# M1-MCU.net
KiCad netlist of a schematic drawn in Altium Designer
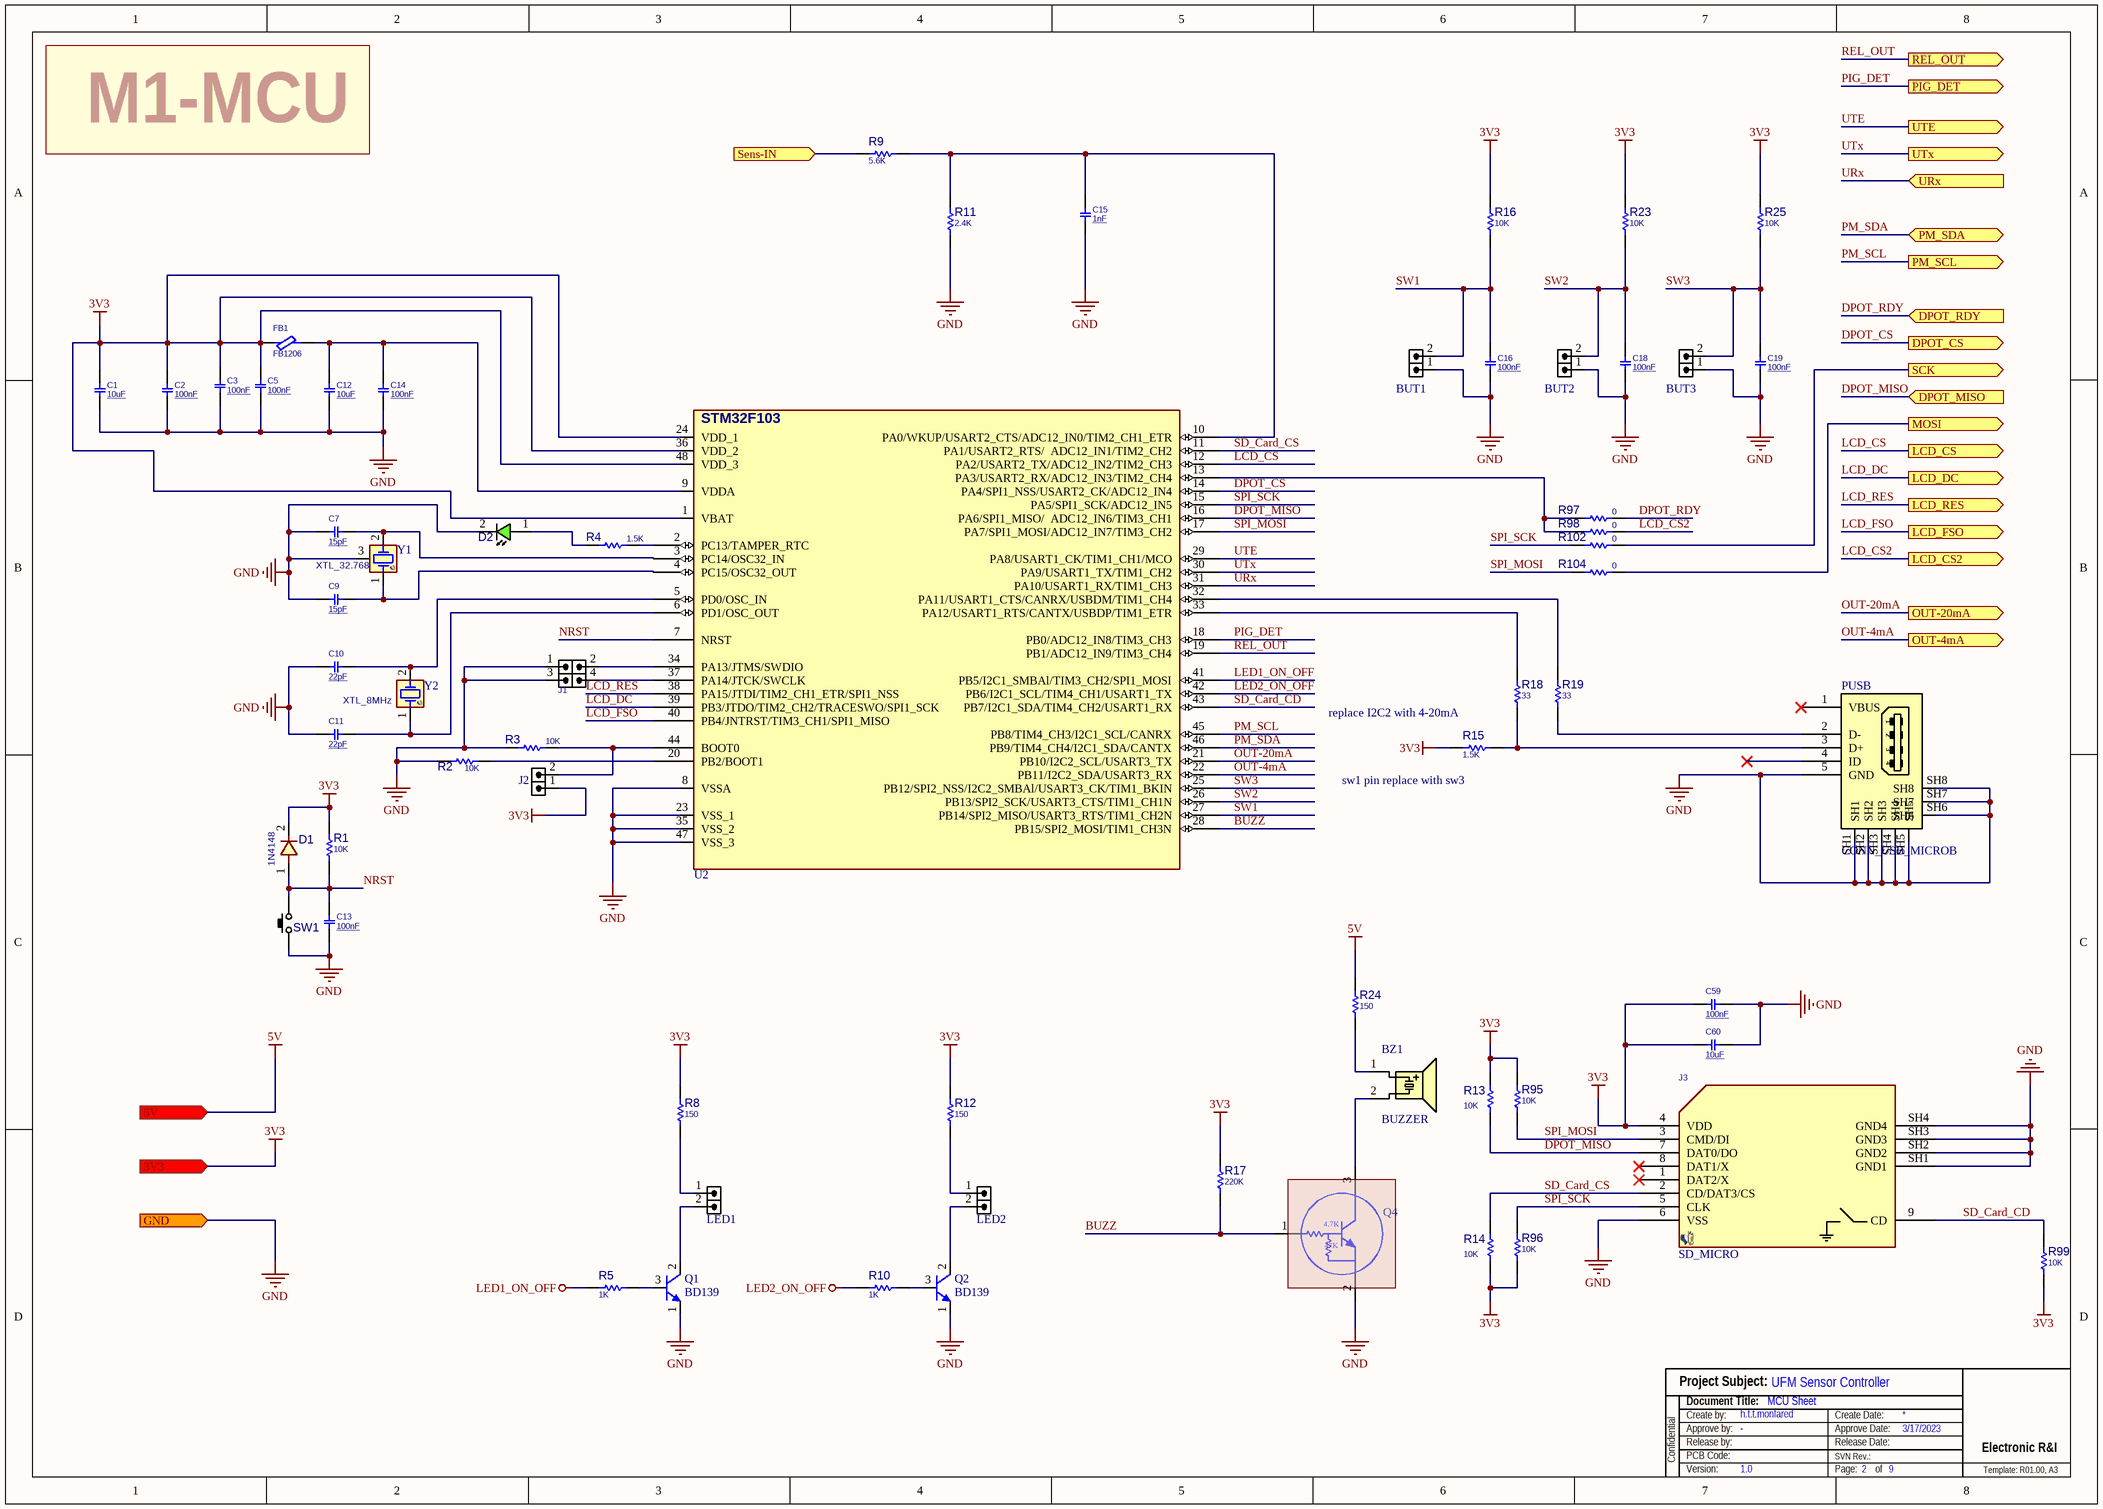
[diagram p0: M1-MCU.SchDoc]

(export (version "E")
  (design (tool "Eeschema 10.0.6"))
  (components
    (comp (ref "BUT1")
      (value "HDRM2")
      (footprint "TMS2")
      (description "CONN, HEADER, Male, pitch: 2.54mm, 2POS")
      (libsource (lib "conn_header_2.54_st") (part "HDR_M_1X2"))
    )
    (comp (ref "BUT2")
      (value "HDRM2")
      (footprint "TMS2")
      (description "CONN, HEADER, Male, pitch: 2.54mm, 2POS")
      (libsource (lib "conn_header_2.54_st") (part "HDR_M_1X2"))
    )
    (comp (ref "BUT3")
      (value "HDRM2")
      (footprint "TMS2")
      (description "CONN, HEADER, Male, pitch: 2.54mm, 2POS")
      (libsource (lib "conn_header_2.54_st") (part "HDR_M_1X2"))
    )
    (comp (ref "BZ1")
      (value "BUZZER")
      (footprint "BZ_C12")
      (description "Buzzer, 12X8.5mm, Magnetic Transducer")
      (fields
        (field (name "MANF") "Buerklin, CUI")
        (field (name "MANF_P#") "CM12P, MT03-H1BHP, BMT1205XH7.5, CEM-1201(50)")
      )
      (libsource (lib "audio_mic_spk") (part "BUZZER_C12"))
    )
    (comp (ref "C1")
      (value "10uF")
      (footprint "C1206")
      (description "CAP, MLCC, 1nF, 50V, C0G, 10%, 0402")
      (fields (field (name "MANF_P#") "MANF_PART#") (field (name "MANF") "Murata"))
      (libsource (lib "passive_smd") (part "CAP_SMD_MLCC"))
    )
    (comp (ref "C2")
      (value "100nF")
      (footprint "C1206")
      (description "CAP, MLCC, 1nF, 50V, C0G, 10%, 0402")
      (fields (field (name "MANF_P#") "MANF_PART#") (field (name "MANF") "Murata"))
      (libsource (lib "passive") (part "CAP_SMD_MLCC"))
    )
    (comp (ref "C3")
      (value "100nF")
      (footprint "C1206")
      (description "CAP, MLCC, 1nF, 50V, C0G, 10%, 0402")
      (fields (field (name "MANF_P#") "MANF_PART#") (field (name "MANF") "Murata"))
      (libsource (lib "passive") (part "CAP_SMD_MLCC"))
    )
    (comp (ref "C5")
      (value "100nF")
      (footprint "C1206")
      (description "CAP, MLCC, 1nF, 50V, C0G, 10%, 0402")
      (fields (field (name "MANF_P#") "MANF_PART#") (field (name "MANF") "Murata"))
      (libsource (lib "passive") (part "CAP_SMD_MLCC"))
    )
    (comp (ref "C7")
      (value "15pF")
      (footprint "C1206")
      (description "CAP, MLCC, 1nF, 50V, C0G, 10%, 0402")
      (fields (field (name "MANF_P#") "MANF_PART#") (field (name "MANF") "Murata"))
      (libsource (lib "passive") (part "CAP_SMD_MLCC"))
    )
    (comp (ref "C9")
      (value "15pF")
      (footprint "C1206")
      (description "CAP, MLCC, 1nF, 50V, C0G, 10%, 0402")
      (fields (field (name "MANF_P#") "MANF_PART#") (field (name "MANF") "Murata"))
      (libsource (lib "passive") (part "CAP_SMD_MLCC"))
    )
    (comp (ref "C10")
      (value "22pF")
      (footprint "C1206")
      (description "CAP, MLCC, 1nF, 50V, C0G, 10%, 0402")
      (fields (field (name "MANF_P#") "MANF_PART#") (field (name "MANF") "Murata"))
      (libsource (lib "passive") (part "CAP_SMD_MLCC"))
    )
    (comp (ref "C11")
      (value "22pF")
      (footprint "C1206")
      (description "CAP, MLCC, 1nF, 50V, C0G, 10%, 0402")
      (fields (field (name "MANF_P#") "MANF_PART#") (field (name "MANF") "Murata"))
      (libsource (lib "passive") (part "CAP_SMD_MLCC"))
    )
    (comp (ref "C12")
      (value "10uF")
      (footprint "C1206")
      (description "CAP, MLCC, 1nF, 50V, C0G, 10%, 0402")
      (fields (field (name "MANF_P#") "MANF_PART#") (field (name "MANF") "Murata"))
      (libsource (lib "passive_smd") (part "CAP_SMD_MLCC"))
    )
    (comp (ref "C13")
      (value "100nF")
      (footprint "C1206")
      (description "CAP, MLCC, 1nF, 50V, C0G, 10%, 0402")
      (fields (field (name "MANF_P#") "MANF_PART#") (field (name "MANF") "Murata"))
      (libsource (lib "passive") (part "CAP_SMD_MLCC"))
    )
    (comp (ref "C14")
      (value "100nF")
      (footprint "C1206")
      (description "CAP, MLCC, 1nF, 50V, C0G, 10%, 0402")
      (fields (field (name "MANF_P#") "MANF_PART#") (field (name "MANF") "Murata"))
      (libsource (lib "passive") (part "CAP_SMD_MLCC"))
    )
    (comp (ref "C15")
      (value "1nF")
      (footprint "C1206")
      (description "CAP, MLCC, 1nF, 50V, C0G, 10%, 0402")
      (fields (field (name "MANF_P#") "MANF_PART#") (field (name "MANF") "Murata"))
      (libsource (lib "passive_smd") (part "CAP_SMD_MLCC"))
    )
    (comp (ref "C16")
      (value "100nF")
      (footprint "C1206")
      (description "CAP, MLCC, 1nF, 50V, C0G, 10%, 0402")
      (fields (field (name "MANF_P#") "MANF_PART#") (field (name "MANF") "Murata"))
      (libsource (lib "passive_smd") (part "CAP_SMD_MLCC"))
    )
    (comp (ref "C18")
      (value "100nF")
      (footprint "C1206")
      (description "CAP, MLCC, 1nF, 50V, C0G, 10%, 0402")
      (fields (field (name "MANF_P#") "MANF_PART#") (field (name "MANF") "Murata"))
      (libsource (lib "passive_smd") (part "CAP_SMD_MLCC"))
    )
    (comp (ref "C19")
      (value "100nF")
      (footprint "C1206")
      (description "CAP, MLCC, 1nF, 50V, C0G, 10%, 0402")
      (fields (field (name "MANF_P#") "MANF_PART#") (field (name "MANF") "Murata"))
      (libsource (lib "passive_smd") (part "CAP_SMD_MLCC"))
    )
    (comp (ref "C59")
      (value "100nF")
      (footprint "C1206")
      (description "CAP, MLCC, 1nF, 50V, C0G, 10%, 0402")
      (fields (field (name "MANF_P#") "MANF_PART#") (field (name "MANF") "Murata"))
      (libsource (lib "passive_smd") (part "CAP_SMD_MLCC"))
    )
    (comp (ref "C60")
      (value "10uF")
      (footprint "C1206")
      (description "CAP, MLCC, 1nF, 50V, C0G, 10%, 0402")
      (fields (field (name "MANF_P#") "MANF_PART#") (field (name "MANF") "Murata"))
      (libsource (lib "passive_smd") (part "CAP_SMD_MLCC"))
    )
    (comp (ref "D1")
      (value "1N4148")
      (footprint "D_AX02_DO35")
      (description "DIODE, FAST SWTICHING, THD")
      (fields (field (name "MANF") "MANF"))
      (libsource (lib "diode") (part "DIODE_THD_1N4148_DO35"))
    )
    (comp (ref "D2")
      (value "LED1206GRN")
      (footprint "LED1206GRN")
      (description "LED, SMD, 1206, GREEN")
      (libsource (lib "led(diode)") (part "LED_SMD_1206_GRN"))
    )
    (comp (ref "FB1")
      (value "FB1206")
      (footprint "L1206")
      (description "FERRITE_Bead, 1206, 6A, 9mOhm, 33@100MHz")
      (fields (field (name "MANF") "Murata") (field (name "MANF_P#") "BLM31PG330SN1L"))
      (libsource (lib "emi_filter") (part "FBEAD_SMD_BLM31PG330"))
    )
    (comp (ref "J1")
      (value "HDRM_2X2")
      (footprint "HDR_M_2X2")
      (description "CONN, HEADER, Male, pitch: 2.54mm, 4POS")
      (fields (field (name "MANF_P#") "MANF_PART#") (field (name "MANF") "MANF"))
      (libsource (lib "conn_header_2.54_st") (part "HDR_M_2X2"))
    )
    (comp (ref "J2")
      (value "HDRM2")
      (footprint "HDR_M_1X2")
      (description "CONN, HEADER, Male, pitch: 2.54mm, 2POS")
      (libsource (lib "conn_header_2.54_st") (part "HDR_M_1X2"))
    )
    (comp (ref "J3")
      (value "SD_MICRO")
      (footprint "SDMICRO_AT")
      (description "SD MICRO exist in Iran, Attend 112J-TDAR-R01")
      (fields (field (name "MANF") "Attend") (field (name "MANF_P#") "112J-TDAR-R01"))
      (libsource (lib "socket_card") (part "SOCKET_SDMICRO_AT"))
    )
    (comp (ref "LED1")
      (value "HDRM2")
      (footprint "TMS2")
      (description "CONN, HEADER, Male, pitch: 2.54mm, 2POS")
      (libsource (lib "") (part "HDR_M_1X2_1"))
    )
    (comp (ref "LED2")
      (value "HDRM2")
      (footprint "TMS2")
      (description "CONN, HEADER, Male, pitch: 2.54mm, 2POS")
      (libsource (lib "") (part "HDR_M_1X2_1"))
    )
    (comp (ref "PUSB")
      (value "CONN_USB_MICROB")
      (footprint "USB_MICRO_B_BM_SHS")
      (description "CONN, USB, MICRO B, R/A, SMD, BOTTOM MOUNT")
      (fields (field (name "MANF_P#") "47346-0001") (field (name "MANF") "Molex"))
      (libsource (lib "conn_usb") (part "CONN_USB_MICRO_B_BM_SHS"))
    )
    (comp (ref "Q1")
      (value "BD139")
      (footprint "TO126_3")
      (description "BJT, NPN, 80V, 1.5A")
      (fields (field (name "MANF") "FAIRCHILD"))
      (libsource (lib "transistor_bjt") (part "NPN_BD139_TO126"))
    )
    (comp (ref "Q2")
      (value "BD139")
      (footprint "TO126_3")
      (description "BJT, NPN, 80V, 1.5A")
      (fields (field (name "MANF") "FAIRCHILD"))
      (libsource (lib "transistor_bjt") (part "NPN_BD139_TO126"))
    )
    (comp (ref "Q4")
      (value "BCR116")
      (footprint "SOT23:SOT23")
      (description "NPN Silicon Digital Transistor")
      (libsource (lib "BCR116") (part "BCR116"))
    )
    (comp (ref "R1")
      (value "10K")
      (footprint "R1206")
      (description "RESISTOR, SMD")
      (fields (field (name "MANF_P#") "RK73H1ETTP4701F") (field (name "MANF") "KOA SPEER"))
      (libsource (lib "passive") (part "RES_SMD"))
    )
    (comp (ref "R2")
      (value "10K")
      (footprint "R1206")
      (description "RESISTOR, SMD")
      (fields (field (name "MANF_P#") "RK73H1ETTP4701F") (field (name "MANF") "KOA SPEER"))
      (libsource (lib "passive") (part "RES_SMD"))
    )
    (comp (ref "R3")
      (value "10K")
      (footprint "R1206")
      (description "RESISTOR, SMD")
      (fields (field (name "MANF_P#") "RK73H1ETTP4701F") (field (name "MANF") "KOA SPEER"))
      (libsource (lib "passive") (part "RES_SMD"))
    )
    (comp (ref "R4")
      (value "1.5K")
      (footprint "R1206")
      (description "RESISTOR, SMD")
      (fields (field (name "MANF_P#") "RK73H1ETTP4701F") (field (name "MANF") "KOA SPEER"))
      (libsource (lib "passive") (part "RES_SMD"))
    )
    (comp (ref "R5")
      (value "1K")
      (footprint "R1206")
      (description "RESISTOR, SMD")
      (fields (field (name "MANF_P#") "RK73H1ETTP4701F") (field (name "MANF") "KOA SPEER"))
      (libsource (lib "passive") (part "RES_SMD"))
    )
    (comp (ref "R8")
      (value "150")
      (footprint "R1206")
      (description "RESISTOR, SMD")
      (fields (field (name "MANF_P#") "RK73H1ETTP4701F") (field (name "MANF") "KOA SPEER"))
      (libsource (lib "passive") (part "RES_SMD"))
    )
    (comp (ref "R9")
      (value "5.6K")
      (footprint "R1206")
      (description "RESISTOR, SMD")
      (libsource (lib "passive_smd") (part "RES_SMD"))
    )
    (comp (ref "R10")
      (value "1K")
      (footprint "R1206")
      (description "RESISTOR, SMD")
      (fields (field (name "MANF_P#") "RK73H1ETTP4701F") (field (name "MANF") "KOA SPEER"))
      (libsource (lib "passive") (part "RES_SMD"))
    )
    (comp (ref "R11")
      (value "2.4K")
      (footprint "R1206")
      (description "RESISTOR, SMD")
      (libsource (lib "passive_smd") (part "RES_SMD"))
    )
    (comp (ref "R12")
      (value "150")
      (footprint "R1206")
      (description "RESISTOR, SMD")
      (fields (field (name "MANF_P#") "RK73H1ETTP4701F") (field (name "MANF") "KOA SPEER"))
      (libsource (lib "passive") (part "RES_SMD"))
    )
    (comp (ref "R13")
      (value "10K")
      (footprint "R1206")
      (description "RESISTOR, SMD")
      (libsource (lib "passive_smd") (part "RES_SMD"))
    )
    (comp (ref "R14")
      (value "10K")
      (footprint "R1206")
      (description "RESISTOR, SMD")
      (libsource (lib "passive_smd") (part "RES_SMD"))
    )
    (comp (ref "R15")
      (value "1.5K")
      (footprint "R1206")
      (description "RESISTOR, SMD")
      (fields (field (name "MANF_P#") "RK73H1ETTP4701F") (field (name "MANF") "KOA SPEER"))
      (libsource (lib "passive") (part "RES_SMD"))
    )
    (comp (ref "R16")
      (value "10K")
      (footprint "R1206")
      (description "RESISTOR, SMD")
      (libsource (lib "passive_smd") (part "RES_SMD"))
    )
    (comp (ref "R17")
      (value "220K")
      (footprint "R1206")
      (description "RESISTOR, SMD")
      (libsource (lib "passive_smd") (part "RES_SMD"))
    )
    (comp (ref "R18")
      (value "33")
      (footprint "R1206")
      (description "RESISTOR, SMD")
      (fields (field (name "MANF_P#") "RK73H1ETTP4701F") (field (name "MANF") "KOA SPEER"))
      (libsource (lib "passive") (part "RES_SMD"))
    )
    (comp (ref "R19")
      (value "33")
      (footprint "R1206")
      (description "RESISTOR, SMD")
      (fields (field (name "MANF_P#") "RK73H1ETTP4701F") (field (name "MANF") "KOA SPEER"))
      (libsource (lib "passive") (part "RES_SMD"))
    )
    (comp (ref "R23")
      (value "10K")
      (footprint "R1206")
      (description "RESISTOR, SMD")
      (libsource (lib "passive_smd") (part "RES_SMD"))
    )
    (comp (ref "R24")
      (value "150")
      (footprint "R1206")
      (description "RESISTOR, SMD")
      (libsource (lib "passive_smd") (part "RES_SMD"))
    )
    (comp (ref "R25")
      (value "10K")
      (footprint "R1206")
      (description "RESISTOR, SMD")
      (libsource (lib "passive_smd") (part "RES_SMD"))
    )
    (comp (ref "R95")
      (value "10K")
      (footprint "R1206")
      (description "RESISTOR, SMD")
      (libsource (lib "passive_smd") (part "RES_SMD"))
    )
    (comp (ref "R96")
      (value "10K")
      (footprint "R1206")
      (description "RESISTOR, SMD")
      (libsource (lib "passive_smd") (part "RES_SMD"))
    )
    (comp (ref "R97")
      (value "0")
      (footprint "R1206")
      (description "RESISTOR, SMD")
      (libsource (lib "passive_smd") (part "RES_SMD"))
    )
    (comp (ref "R98")
      (value "0")
      (footprint "R1206")
      (description "RESISTOR, SMD")
      (libsource (lib "passive_smd") (part "RES_SMD"))
    )
    (comp (ref "R99")
      (value "10K")
      (footprint "R1206")
      (description "RESISTOR, SMD")
      (libsource (lib "passive_smd") (part "RES_SMD"))
    )
    (comp (ref "R102")
      (value "0")
      (footprint "R1206")
      (description "RESISTOR, SMD")
      (libsource (lib "passive_smd") (part "RES_SMD"))
    )
    (comp (ref "R104")
      (value "0")
      (footprint "R1206")
      (description "RESISTOR, SMD")
      (libsource (lib "passive_smd") (part "RES_SMD"))
    )
    (comp (ref "SW1")
      (value "PUSHBUTTON")
      (footprint "SWPBS_SPST_6X3X5")
      (description "SWITCH, PUSH BUTTON, TACTILE, SMD, SPST, 6X3.5X4.3mm")
      (fields (field (name "MANF") "Panasonic") (field (name "MANF_P#") "EVQ-PNF04M"))
      (libsource (lib "switch_tact_PUSHB") (part "SWPBS_SPST_6X3X4"))
    )
    (comp (ref "U2")
      (value "STM32F103")
      (footprint "QFG50_48")
      (description "MCU, STM32 ARM 32-bit, Cortex M3, 64KB FLASH, 20KB SRAM")
      (fields (field (name "MANF") "ST") (field (name "MANF_P#") "STM32F103C8T6"))
      (libsource (lib "mcu_stm32") (part "STM32F103C8T6_QFP48"))
    )
    (comp (ref "Y1")
      (value "XTL_32.768")
      (footprint "XTLT_RTC")
      (description "Crystal MOST POPULAR PACKAGE")
      (fields (field (name "MANF") "ABRACON") (field (name "MANF_P#") "AB26T-32.768KHZ"))
      (libsource (lib "crystal") (part "XTL_3_32.768_THD"))
    )
    (comp (ref "Y2")
      (value "XTL_8MHz")
      (footprint "XTL_2_11X5")
      (description "Crystal MOST POPULAR ABL HC49 PACKAGE")
      (fields (field (name "MANF") "ABRACON") (field (name "MANF_P#") "ABLS-8.000MHZ-B4-T"))
      (libsource (lib "crystal") (part "XTL_2_HC49_8MHz_SMD"))
    )
  )
  (nets
    (net (code "1") (name "/BUZZ") (class "Default")
      (node (ref "Q4") (pin "1") (pinfunction "B_1") (pintype "passive"))
      (node (ref "R17") (pin "1") (pinfunction "1_1") (pintype "passive"))
      (node (ref "U2") (pin "28") (pinfunction "PB15/SPI2_MOSI/TIM1_CH3N_28") (pintype "bidirectional"))
    )
    (net (code "2") (name "/DPOT_CS") (class "Default")
      (node (ref "U2") (pin "14") (pinfunction "PA4/SPI1_NSS/USART2_CK/ADC12_IN4_14") (pintype "bidirectional"))
    )
    (net (code "3") (name "/DPOT_MISO") (class "Default")
      (node (ref "J3") (pin "7") (pinfunction "DAT0/DO_7") (pintype "passive"))
      (node (ref "R13") (pin "1") (pinfunction "1_1") (pintype "passive"))
      (node (ref "U2") (pin "16") (pinfunction "PA6/SPI1_MISO/__ADC12_IN6/TIM3_CH1_16") (pintype "bidirectional"))
    )
    (net (code "4") (name "/DPOT_RDY") (class "Default")
      (node (ref "R97") (pin "2") (pinfunction "2_2") (pintype "passive"))
    )
    (net (code "5") (name "/LCD_CS") (class "Default")
      (node (ref "U2") (pin "12") (pinfunction "PA2/USART2_TX/ADC12_IN2/TIM2_CH3_12") (pintype "bidirectional"))
    )
    (net (code "6") (name "/LCD_CS2") (class "Default")
      (node (ref "R98") (pin "2") (pinfunction "2_2") (pintype "passive"))
    )
    (net (code "7") (name "/LCD_DC") (class "Default")
      (node (ref "U2") (pin "39") (pinfunction "PB3/JTDO/TIM2_CH2/TRACESWO/SPI1_SCK_39") (pintype "passive"))
    )
    (net (code "8") (name "/LCD_FSO") (class "Default")
      (node (ref "U2") (pin "40") (pinfunction "PB4/JNTRST/TIM3_CH1/SPI1_MISO_40") (pintype "passive"))
    )
    (net (code "9") (name "/LCD_RES") (class "Default")
      (node (ref "U2") (pin "38") (pinfunction "PA15/JTDI/TIM2_CH1_ETR/SPI1_NSS_38") (pintype "passive"))
    )
    (net (code "10") (name "/MOSI") (class "Default")
      (node (ref "R104") (pin "2") (pinfunction "2_2") (pintype "passive"))
    )
    (net (code "11") (name "/NRST") (class "Default")
      (node (ref "C13") (pin "2") (pinfunction "2_2") (pintype "passive"))
      (node (ref "D1") (pin "1") (pinfunction "1_1") (pintype "passive"))
      (node (ref "R1") (pin "1") (pinfunction "1_1") (pintype "passive"))
      (node (ref "SW1") (pin "2") (pinfunction "P3_2") (pintype "passive"))
      (node (ref "U2") (pin "7") (pinfunction "NRST_7") (pintype "passive"))
    )
    (net (code "12") (name "/OUT-4mA") (class "Default")
      (node (ref "U2") (pin "22") (pinfunction "PB11/I2C2_SDA/USART3_RX_22") (pintype "bidirectional"))
    )
    (net (code "13") (name "/OUT-20mA") (class "Default")
      (node (ref "U2") (pin "21") (pinfunction "PB10/I2C2_SCL/USART3_TX_21") (pintype "bidirectional"))
    )
    (net (code "14") (name "/PIG_DET") (class "Default")
      (node (ref "U2") (pin "18") (pinfunction "PB0/ADC12_IN8/TIM3_CH3_18") (pintype "bidirectional"))
    )
    (net (code "15") (name "/PM_SCL") (class "Default")
      (node (ref "U2") (pin "45") (pinfunction "PB8/TIM4_CH3/I2C1_SCL/CANRX_45") (pintype "bidirectional"))
    )
    (net (code "16") (name "/PM_SDA") (class "Default")
      (node (ref "U2") (pin "46") (pinfunction "PB9/TIM4_CH4/I2C1_SDA/CANTX_46") (pintype "bidirectional"))
    )
    (net (code "17") (name "/REL_OUT") (class "Default")
      (node (ref "U2") (pin "19") (pinfunction "PB1/ADC12_IN9/TIM3_CH4_19") (pintype "bidirectional"))
    )
    (net (code "18") (name "/SCK") (class "Default")
      (node (ref "R102") (pin "2") (pinfunction "2_2") (pintype "passive"))
    )
    (net (code "19") (name "/SD_Card_CD") (class "Default")
      (node (ref "J3") (pin "9") (pinfunction "CD_9") (pintype "passive"))
      (node (ref "R99") (pin "2") (pinfunction "2_2") (pintype "passive"))
      (node (ref "U2") (pin "43") (pinfunction "PB7/I2C1_SDA/TIM4_CH2/USART1_RX_43") (pintype "bidirectional"))
    )
    (net (code "20") (name "/SD_Card_CS") (class "Default")
      (node (ref "J3") (pin "2") (pinfunction "CD/DAT3/CS_2") (pintype "passive"))
      (node (ref "R14") (pin "2") (pinfunction "2_2") (pintype "passive"))
      (node (ref "U2") (pin "11") (pinfunction "PA1/USART2_RTS/__ADC12_IN1/TIM2_CH2_11") (pintype "bidirectional"))
    )
    (net (code "21") (name "/SPI_MOSI") (class "Default")
      (node (ref "J3") (pin "3") (pinfunction "CMD/DI_3") (pintype "passive"))
      (node (ref "R104") (pin "1") (pinfunction "1_1") (pintype "passive"))
      (node (ref "R95") (pin "1") (pinfunction "1_1") (pintype "passive"))
      (node (ref "U2") (pin "17") (pinfunction "PA7/SPI1_MOSI/ADC12_IN7/TIM3_CH2_17") (pintype "bidirectional"))
    )
    (net (code "22") (name "/SPI_SCK") (class "Default")
      (node (ref "J3") (pin "5") (pinfunction "CLK_5") (pintype "passive"))
      (node (ref "R102") (pin "1") (pinfunction "1_1") (pintype "passive"))
      (node (ref "R96") (pin "2") (pinfunction "2_2") (pintype "passive"))
      (node (ref "U2") (pin "15") (pinfunction "PA5/SPI1_SCK/ADC12_IN5_15") (pintype "bidirectional"))
    )
    (net (code "23") (name "/SW1") (class "Default")
      (node (ref "BUT1") (pin "2") (pinfunction "2_2") (pintype "passive"))
      (node (ref "C16") (pin "2") (pinfunction "2_2") (pintype "passive"))
      (node (ref "R16") (pin "1") (pinfunction "1_1") (pintype "passive"))
      (node (ref "U2") (pin "27") (pinfunction "PB14/SPI2_MISO/USART3_RTS/TIM1_CH2N_27") (pintype "bidirectional"))
    )
    (net (code "24") (name "/SW2") (class "Default")
      (node (ref "BUT2") (pin "2") (pinfunction "2_2") (pintype "passive"))
      (node (ref "C18") (pin "2") (pinfunction "2_2") (pintype "passive"))
      (node (ref "R23") (pin "1") (pinfunction "1_1") (pintype "passive"))
      (node (ref "U2") (pin "26") (pinfunction "PB13/SPI2_SCK/USART3_CTS/TIM1_CH1N_26") (pintype "bidirectional"))
    )
    (net (code "25") (name "/SW3") (class "Default")
      (node (ref "BUT3") (pin "2") (pinfunction "2_2") (pintype "passive"))
      (node (ref "C19") (pin "2") (pinfunction "2_2") (pintype "passive"))
      (node (ref "R25") (pin "1") (pinfunction "1_1") (pintype "passive"))
      (node (ref "U2") (pin "25") (pinfunction "PB12/SPI2_NSS/I2C2_SMBAl/USART3_CK/TIM1_BKIN_25") (pintype "bidirectional"))
    )
    (net (code "26") (name "/Sens-IN") (class "Default")
      (node (ref "R9") (pin "1") (pinfunction "1_1") (pintype "passive"))
    )
    (net (code "27") (name "/URx") (class "Default")
      (node (ref "U2") (pin "31") (pinfunction "PA10/USART1_RX/TIM1_CH3_31") (pintype "bidirectional"))
    )
    (net (code "28") (name "/UTE") (class "Default")
      (node (ref "U2") (pin "29") (pinfunction "PA8/USART1_CK/TIM1_CH1/MCO_29") (pintype "bidirectional"))
    )
    (net (code "29") (name "/UTx") (class "Default")
      (node (ref "U2") (pin "30") (pinfunction "PA9/USART1_TX/TIM1_CH2_30") (pintype "bidirectional"))
    )
    (net (code "30") (name "3V3") (class "Default")
      (node (ref "C1") (pin "2") (pinfunction "2_2") (pintype "passive"))
      (node (ref "C2") (pin "2") (pinfunction "2_2") (pintype "passive"))
      (node (ref "C3") (pin "2") (pinfunction "2_2") (pintype "passive"))
      (node (ref "C5") (pin "2") (pinfunction "2_2") (pintype "passive"))
      (node (ref "C59") (pin "1") (pinfunction "1_1") (pintype "passive"))
      (node (ref "C60") (pin "1") (pinfunction "1_1") (pintype "passive"))
      (node (ref "D1") (pin "2") (pinfunction "2_2") (pintype "passive"))
      (node (ref "FB1") (pin "1") (pinfunction "1_1") (pintype "passive"))
      (node (ref "J2") (pin "1") (pinfunction "1_1") (pintype "passive"))
      (node (ref "J3") (pin "4") (pinfunction "VDD_4") (pintype "passive"))
      (node (ref "R1") (pin "2") (pinfunction "2_2") (pintype "passive"))
      (node (ref "R12") (pin "2") (pinfunction "2_2") (pintype "passive"))
      (node (ref "R13") (pin "2") (pinfunction "2_2") (pintype "passive"))
      (node (ref "R14") (pin "1") (pinfunction "1_1") (pintype "passive"))
      (node (ref "R15") (pin "1") (pinfunction "1_1") (pintype "passive"))
      (node (ref "R16") (pin "2") (pinfunction "2_2") (pintype "passive"))
      (node (ref "R17") (pin "2") (pinfunction "2_2") (pintype "passive"))
      (node (ref "R23") (pin "2") (pinfunction "2_2") (pintype "passive"))
      (node (ref "R25") (pin "2") (pinfunction "2_2") (pintype "passive"))
      (node (ref "R8") (pin "2") (pinfunction "2_2") (pintype "passive"))
      (node (ref "R95") (pin "2") (pinfunction "2_2") (pintype "passive"))
      (node (ref "R96") (pin "1") (pinfunction "1_1") (pintype "passive"))
      (node (ref "R99") (pin "1") (pinfunction "1_1") (pintype "passive"))
      (node (ref "U2") (pin "1") (pinfunction "VBAT_1") (pintype "passive"))
      (node (ref "U2") (pin "24") (pinfunction "VDD_1_24") (pintype "passive"))
      (node (ref "U2") (pin "36") (pinfunction "VDD_2_36") (pintype "passive"))
      (node (ref "U2") (pin "48") (pinfunction "VDD_3_48") (pintype "passive"))
    )
    (net (code "31") (name "5V") (class "Default")
      (node (ref "R24") (pin "2") (pinfunction "2_2") (pintype "passive"))
    )
    (net (code "32") (name "GND") (class "Default")
      (node (ref "BUT1") (pin "1") (pinfunction "1_1") (pintype "passive"))
      (node (ref "BUT2") (pin "1") (pinfunction "1_1") (pintype "passive"))
      (node (ref "BUT3") (pin "1") (pinfunction "1_1") (pintype "passive"))
      (node (ref "C1") (pin "1") (pinfunction "1_1") (pintype "passive"))
      (node (ref "C10") (pin "1") (pinfunction "1_1") (pintype "passive"))
      (node (ref "C11") (pin "1") (pinfunction "1_1") (pintype "passive"))
      (node (ref "C12") (pin "2") (pinfunction "2_2") (pintype "passive"))
      (node (ref "C13") (pin "1") (pinfunction "1_1") (pintype "passive"))
      (node (ref "C14") (pin "1") (pinfunction "1_1") (pintype "passive"))
      (node (ref "C15") (pin "1") (pinfunction "1_1") (pintype "passive"))
      (node (ref "C16") (pin "1") (pinfunction "1_1") (pintype "passive"))
      (node (ref "C18") (pin "1") (pinfunction "1_1") (pintype "passive"))
      (node (ref "C19") (pin "1") (pinfunction "1_1") (pintype "passive"))
      (node (ref "C2") (pin "1") (pinfunction "1_1") (pintype "passive"))
      (node (ref "C3") (pin "1") (pinfunction "1_1") (pintype "passive"))
      (node (ref "C5") (pin "1") (pinfunction "1_1") (pintype "passive"))
      (node (ref "C59") (pin "2") (pinfunction "2_2") (pintype "passive"))
      (node (ref "C60") (pin "2") (pinfunction "2_2") (pintype "passive"))
      (node (ref "C7") (pin "1") (pinfunction "1_1") (pintype "passive"))
      (node (ref "C9") (pin "1") (pinfunction "1_1") (pintype "passive"))
      (node (ref "D2") (pin "2") (pinfunction "CATHODE_2") (pintype "passive"))
      (node (ref "J1") (pin "1") (pinfunction "1_1") (pintype "passive"))
      (node (ref "J1") (pin "3") (pinfunction "3_3") (pintype "passive"))
      (node (ref "J3") (pin "6") (pinfunction "VSS_6") (pintype "passive"))
      (node (ref "J3") (pin "SH1") (pinfunction "GND1_SH1") (pintype "passive"))
      (node (ref "J3") (pin "SH2") (pinfunction "GND2_SH2") (pintype "passive"))
      (node (ref "J3") (pin "SH3") (pinfunction "GND3_SH3") (pintype "passive"))
      (node (ref "J3") (pin "SH4") (pinfunction "GND4_SH4") (pintype "passive"))
      (node (ref "PUSB") (pin "5") (pinfunction "GND_5") (pintype "power_in"))
      (node (ref "PUSB") (pin "SH1") (pinfunction "SH1_SH1") (pintype "passive"))
      (node (ref "PUSB") (pin "SH2") (pinfunction "SH2_SH2") (pintype "passive"))
      (node (ref "PUSB") (pin "SH3") (pinfunction "SH3_SH3") (pintype "passive"))
      (node (ref "PUSB") (pin "SH4") (pinfunction "SH4_SH4") (pintype "passive"))
      (node (ref "PUSB") (pin "SH5") (pinfunction "SH5_SH5") (pintype "passive"))
      (node (ref "PUSB") (pin "SH6") (pinfunction "SH6_SH6") (pintype "passive"))
      (node (ref "PUSB") (pin "SH7") (pinfunction "SH7_SH7") (pintype "passive"))
      (node (ref "PUSB") (pin "SH8") (pinfunction "SH8_SH8") (pintype "passive"))
      (node (ref "Q1") (pin "1") (pinfunction "E_1") (pintype "passive"))
      (node (ref "Q2") (pin "1") (pinfunction "E_1") (pintype "passive"))
      (node (ref "Q4") (pin "2") (pinfunction "E_2") (pintype "passive"))
      (node (ref "R11") (pin "1") (pinfunction "1_1") (pintype "passive"))
      (node (ref "R2") (pin "1") (pinfunction "1_1") (pintype "passive"))
      (node (ref "R3") (pin "1") (pinfunction "1_1") (pintype "passive"))
      (node (ref "SW1") (pin "1") (pinfunction "P1_1") (pintype "passive"))
      (node (ref "U2") (pin "23") (pinfunction "VSS_1_23") (pintype "passive"))
      (node (ref "U2") (pin "35") (pinfunction "VSS_2_35") (pintype "passive"))
      (node (ref "U2") (pin "47") (pinfunction "VSS_3_47") (pintype "passive"))
      (node (ref "U2") (pin "8") (pinfunction "VSSA_8") (pintype "passive"))
      (node (ref "Y1") (pin "3") (pinfunction "CASE_3") (pintype "passive"))
    )
    (net (code "33") (name "LED1_ON_OFF") (class "Default")
      (node (ref "R5") (pin "1") (pinfunction "1_1") (pintype "passive"))
      (node (ref "U2") (pin "41") (pinfunction "PB5/I2C1_SMBAl/TIM3_CH2/SPI1_MOSI_41") (pintype "bidirectional"))
    )
    (net (code "34") (name "LED2_ON_OFF") (class "Default")
      (node (ref "R10") (pin "1") (pinfunction "1_1") (pintype "passive"))
      (node (ref "U2") (pin "42") (pinfunction "PB6/I2C1_SCL/TIM4_CH1/USART1_TX_42") (pintype "bidirectional"))
    )
    (net (code "35") (name "Net-(BZ1-A)") (class "Default")
      (node (ref "BZ1") (pin "1") (pinfunction "A_1") (pintype "passive"))
      (node (ref "R24") (pin "1") (pinfunction "1_1") (pintype "passive"))
    )
    (net (code "36") (name "Net-(BZ1-B)") (class "Default")
      (node (ref "BZ1") (pin "2") (pinfunction "B_2") (pintype "passive"))
      (node (ref "Q4") (pin "3") (pinfunction "C_3") (pintype "passive"))
    )
    (net (code "37") (name "Net-(D2-ANODE)") (class "Default")
      (node (ref "D2") (pin "1") (pinfunction "ANODE_1") (pintype "passive"))
      (node (ref "R4") (pin "1") (pinfunction "1_1") (pintype "passive"))
    )
    (net (code "38") (name "Net-(LED1-Pad1)") (class "Default")
      (node (ref "LED1") (pin "1") (pinfunction "1_1") (pintype "passive"))
      (node (ref "R8") (pin "1") (pinfunction "1_1") (pintype "passive"))
    )
    (net (code "39") (name "Net-(LED2-Pad1)") (class "Default")
      (node (ref "LED2") (pin "1") (pinfunction "1_1") (pintype "passive"))
      (node (ref "R12") (pin "1") (pinfunction "1_1") (pintype "passive"))
    )
    (net (code "40") (name "Net-(PUSB-D+)") (class "Default")
      (node (ref "PUSB") (pin "3") (pinfunction "D+_3") (pintype "passive"))
      (node (ref "R15") (pin "2") (pinfunction "2_2") (pintype "passive"))
      (node (ref "R18") (pin "1") (pinfunction "1_1") (pintype "passive"))
    )
    (net (code "41") (name "Net-(PUSB-D-)") (class "Default")
      (node (ref "PUSB") (pin "2") (pinfunction "D-_2") (pintype "passive"))
      (node (ref "R19") (pin "1") (pinfunction "1_1") (pintype "passive"))
    )
    (net (code "42") (name "Net-(Q1-B)") (class "Default")
      (node (ref "Q1") (pin "3") (pinfunction "B_3") (pintype "passive"))
      (node (ref "R5") (pin "2") (pinfunction "2_2") (pintype "passive"))
    )
    (net (code "43") (name "Net-(Q1-C)") (class "Default")
      (node (ref "LED1") (pin "2") (pinfunction "2_2") (pintype "passive"))
      (node (ref "Q1") (pin "2") (pinfunction "C_2") (pintype "passive"))
    )
    (net (code "44") (name "Net-(Q2-B)") (class "Default")
      (node (ref "Q2") (pin "3") (pinfunction "B_3") (pintype "passive"))
      (node (ref "R10") (pin "2") (pinfunction "2_2") (pintype "passive"))
    )
    (net (code "45") (name "Net-(Q2-C)") (class "Default")
      (node (ref "LED2") (pin "2") (pinfunction "2_2") (pintype "passive"))
      (node (ref "Q2") (pin "2") (pinfunction "C_2") (pintype "passive"))
    )
    (net (code "46") (name "Net-(U2-BOOT0)") (class "Default")
      (node (ref "J2") (pin "2") (pinfunction "2_2") (pintype "passive"))
      (node (ref "R3") (pin "2") (pinfunction "2_2") (pintype "passive"))
      (node (ref "U2") (pin "44") (pinfunction "BOOT0_44") (pintype "passive"))
    )
    (net (code "47") (name "Net-(U2-PA0{slash}WKUP{slash}USART2_CTS{slash}ADC12_IN0{slash}TIM2_CH1_ETR)") (class "Default")
      (node (ref "C15") (pin "2") (pinfunction "2_2") (pintype "passive"))
      (node (ref "R11") (pin "2") (pinfunction "2_2") (pintype "passive"))
      (node (ref "R9") (pin "2") (pinfunction "2_2") (pintype "passive"))
      (node (ref "U2") (pin "10") (pinfunction "PA0/WKUP/USART2_CTS/ADC12_IN0/TIM2_CH1_ETR_10") (pintype "bidirectional"))
    )
    (net (code "48") (name "Net-(U2-PA3{slash}USART2_RX{slash}ADC12_IN3{slash}TIM2_CH4)") (class "Default")
      (node (ref "R97") (pin "1") (pinfunction "1_1") (pintype "passive"))
      (node (ref "R98") (pin "1") (pinfunction "1_1") (pintype "passive"))
      (node (ref "U2") (pin "13") (pinfunction "PA3/USART2_RX/ADC12_IN3/TIM2_CH4_13") (pintype "bidirectional"))
    )
    (net (code "49") (name "Net-(U2-PA11{slash}USART1_CTS{slash}CANRX{slash}USBDM{slash}TIM1_CH4)") (class "Default")
      (node (ref "R19") (pin "2") (pinfunction "2_2") (pintype "passive"))
      (node (ref "U2") (pin "32") (pinfunction "PA11/USART1_CTS/CANRX/USBDM/TIM1_CH4_32") (pintype "bidirectional"))
    )
    (net (code "50") (name "Net-(U2-PA12{slash}USART1_RTS{slash}CANTX{slash}USBDP{slash}TIM1_ETR)") (class "Default")
      (node (ref "R18") (pin "2") (pinfunction "2_2") (pintype "passive"))
      (node (ref "U2") (pin "33") (pinfunction "PA12/USART1_RTS/CANTX/USBDP/TIM1_ETR_33") (pintype "bidirectional"))
    )
    (net (code "51") (name "Net-(U2-PA13{slash}JTMS{slash}SWDIO)") (class "Default")
      (node (ref "J1") (pin "2") (pinfunction "2_2") (pintype "passive"))
      (node (ref "U2") (pin "34") (pinfunction "PA13/JTMS/SWDIO_34") (pintype "passive"))
    )
    (net (code "52") (name "Net-(U2-PA14{slash}JTCK{slash}SWCLK)") (class "Default")
      (node (ref "J1") (pin "4") (pinfunction "4_4") (pintype "passive"))
      (node (ref "U2") (pin "37") (pinfunction "PA14/JTCK/SWCLK_37") (pintype "passive"))
    )
    (net (code "53") (name "Net-(U2-PB2{slash}BOOT1)") (class "Default")
      (node (ref "R2") (pin "2") (pinfunction "2_2") (pintype "passive"))
      (node (ref "U2") (pin "20") (pinfunction "PB2/BOOT1_20") (pintype "passive"))
    )
    (net (code "54") (name "Net-(U2-PC13{slash}TAMPER_RTC)") (class "Default")
      (node (ref "R4") (pin "2") (pinfunction "2_2") (pintype "passive"))
      (node (ref "U2") (pin "2") (pinfunction "PC13/TAMPER_RTC_2") (pintype "bidirectional"))
    )
    (net (code "55") (name "Net-(U2-PC14{slash}OSC32_IN)") (class "Default")
      (node (ref "C7") (pin "2") (pinfunction "2_2") (pintype "passive"))
      (node (ref "U2") (pin "3") (pinfunction "PC14/OSC32_IN_3") (pintype "bidirectional"))
      (node (ref "Y1") (pin "2") (pinfunction "OSC2_2") (pintype "passive"))
    )
    (net (code "56") (name "Net-(U2-PC15{slash}OSC32_OUT)") (class "Default")
      (node (ref "C9") (pin "2") (pinfunction "2_2") (pintype "passive"))
      (node (ref "U2") (pin "4") (pinfunction "PC15/OSC32_OUT_4") (pintype "bidirectional"))
      (node (ref "Y1") (pin "1") (pinfunction "OSC1_1") (pintype "passive"))
    )
    (net (code "57") (name "Net-(U2-PD0{slash}OSC_IN)") (class "Default")
      (node (ref "C10") (pin "2") (pinfunction "2_2") (pintype "passive"))
      (node (ref "U2") (pin "5") (pinfunction "PD0/OSC_IN_5") (pintype "bidirectional"))
      (node (ref "Y2") (pin "2") (pinfunction "OSC2_2") (pintype "passive"))
    )
    (net (code "58") (name "Net-(U2-PD1{slash}OSC_OUT)") (class "Default")
      (node (ref "C11") (pin "2") (pinfunction "2_2") (pintype "passive"))
      (node (ref "U2") (pin "6") (pinfunction "PD1/OSC_OUT_6") (pintype "bidirectional"))
      (node (ref "Y2") (pin "1") (pinfunction "OSC1_1") (pintype "passive"))
    )
    (net (code "59") (name "Net-(U2-VDDA)") (class "Default")
      (node (ref "C12") (pin "1") (pinfunction "1_1") (pintype "passive"))
      (node (ref "C14") (pin "2") (pinfunction "2_2") (pintype "passive"))
      (node (ref "FB1") (pin "2") (pinfunction "2_2") (pintype "passive"))
      (node (ref "U2") (pin "9") (pinfunction "VDDA_9") (pintype "passive"))
    )
    (net (code "60") (name "unconnected-(J3-DAT1{slash}X-Pad8)") (class "Default")
      (node (ref "J3") (pin "8") (pinfunction "DAT1/X_8") (pintype "passive+no_connect"))
    )
    (net (code "61") (name "unconnected-(J3-DAT2{slash}X-Pad1)") (class "Default")
      (node (ref "J3") (pin "1") (pinfunction "DAT2/X_1") (pintype "passive+no_connect"))
    )
    (net (code "62") (name "unconnected-(PUSB-ID-Pad4)") (class "Default")
      (node (ref "PUSB") (pin "4") (pinfunction "ID_4") (pintype "power_in+no_connect"))
    )
    (net (code "63") (name "unconnected-(PUSB-VBUS-Pad1)") (class "Default")
      (node (ref "PUSB") (pin "1") (pinfunction "VBUS_1") (pintype "power_in+no_connect"))
    )
  )
)
